# wespi-nano_3.net
KiCad netlist of a schematic drawn in EAGLE
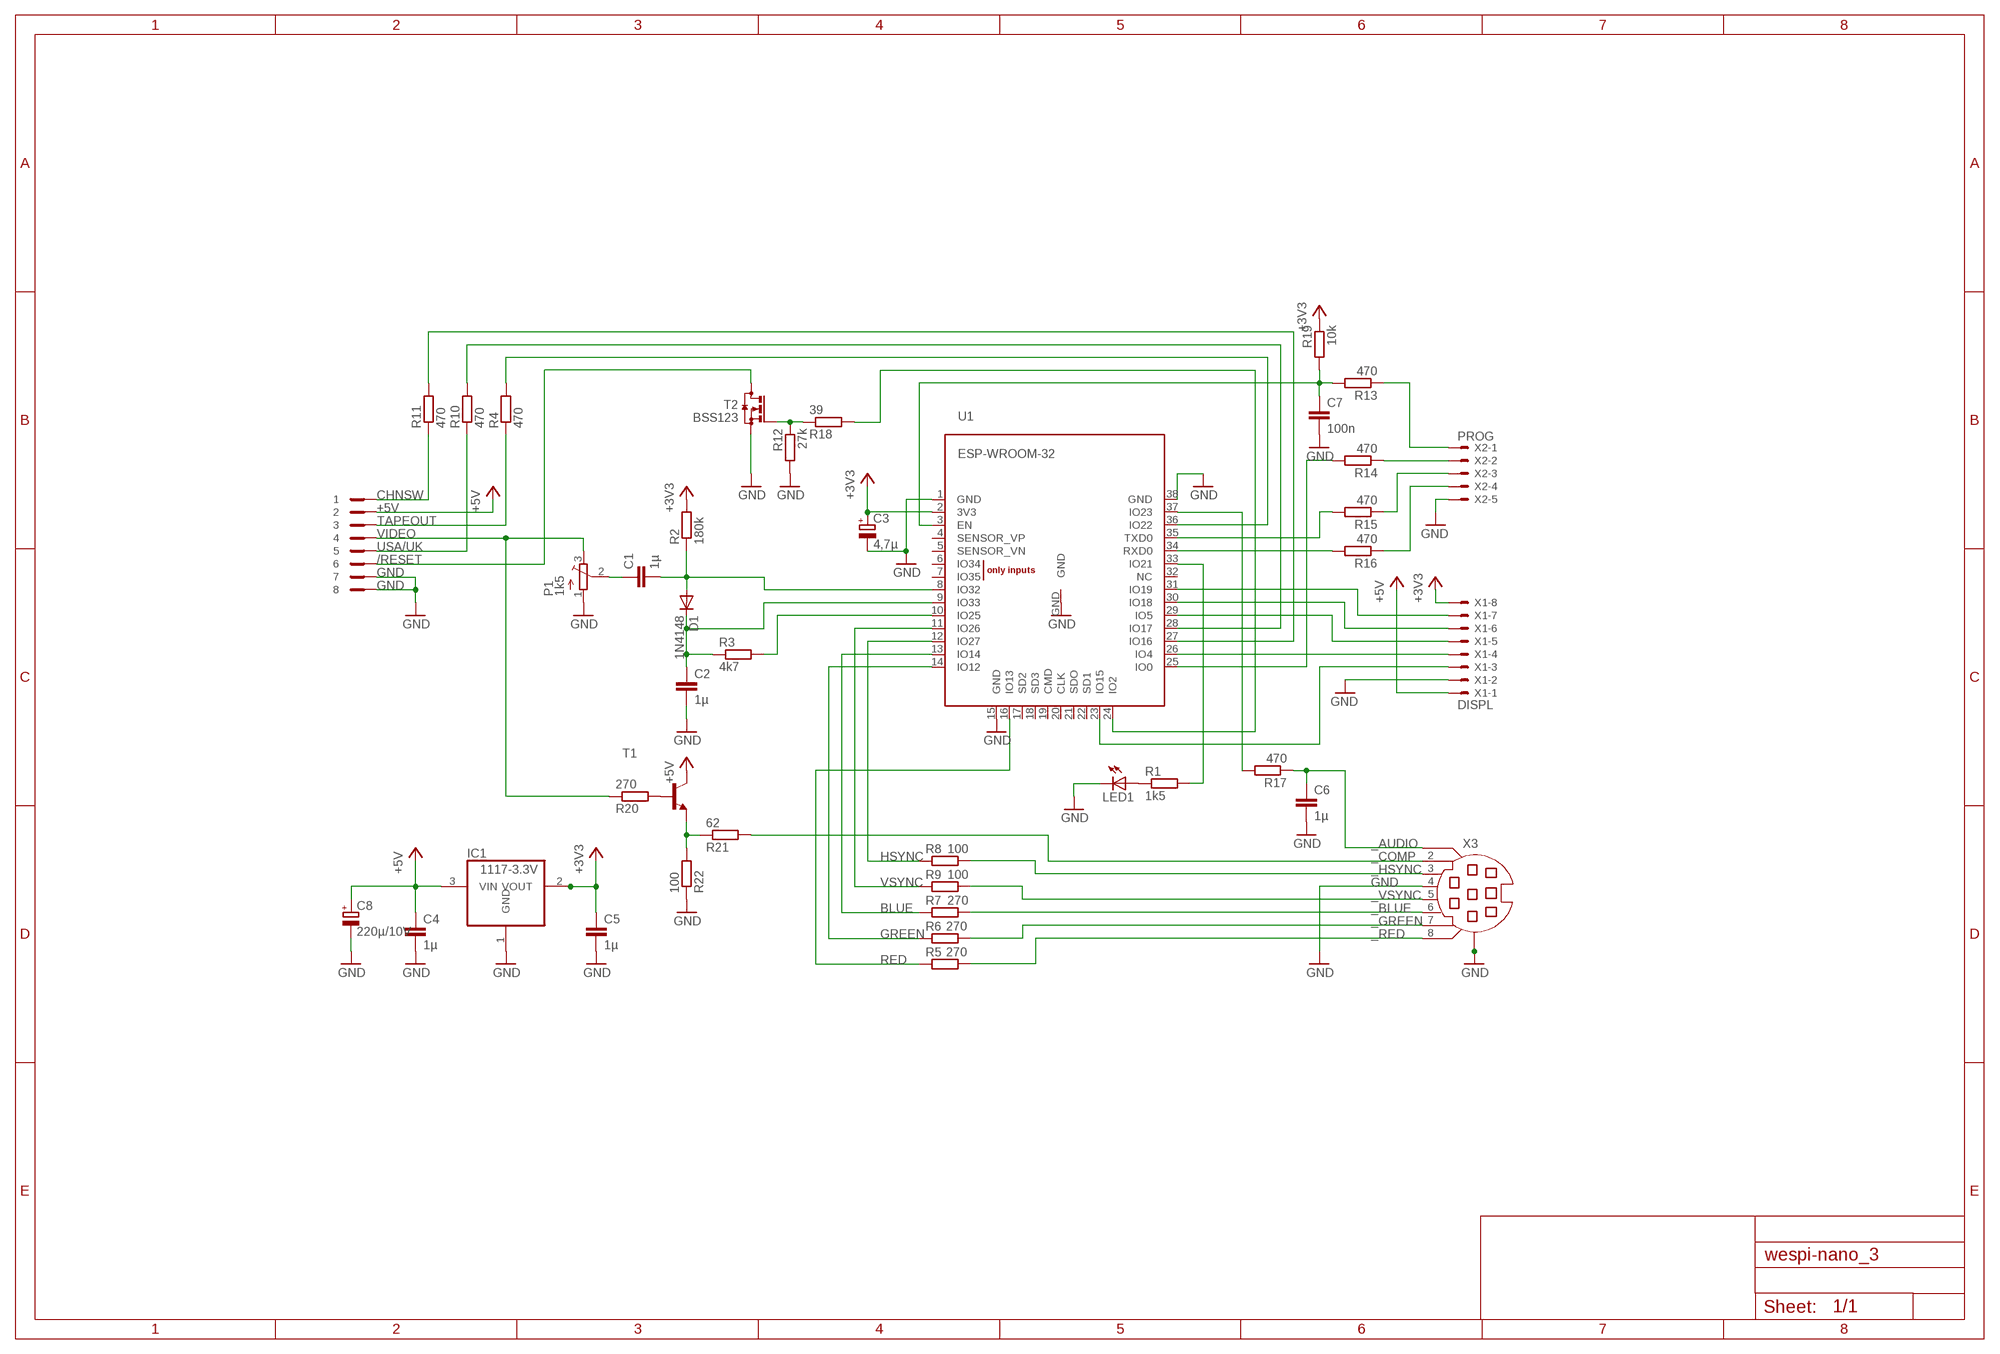
[diagram p0: schematic, sheet 1]

(export (version "E")
  (design (tool "Eeschema 10.0.6"))
  (components
    (comp (ref "C1")
      (value "1µ")
      (footprint "eagle-import:C0805")
      (libsource (lib "eagle-import") (part "C-EUC0805"))
    )
    (comp (ref "C2")
      (value "1µ")
      (footprint "eagle-import:C0805")
      (libsource (lib "eagle-import") (part "C-EUC0805"))
    )
    (comp (ref "C3")
      (value "4,7µ")
      (footprint "eagle-import:153CLV-0405")
      (libsource (lib "eagle-import") (part "CPOL-EU153CLV-0405"))
    )
    (comp (ref "C4")
      (value "1µ")
      (footprint "eagle-import:C0805")
      (libsource (lib "eagle-import") (part "C-EUC0805"))
    )
    (comp (ref "C5")
      (value "1µ")
      (footprint "eagle-import:C0805")
      (libsource (lib "eagle-import") (part "C-EUC0805"))
    )
    (comp (ref "C6")
      (value "1µ")
      (footprint "eagle-import:C0805")
      (libsource (lib "eagle-import") (part "C-EUC0805"))
    )
    (comp (ref "C7")
      (value "100n")
      (footprint "eagle-import:C0805")
      (libsource (lib "eagle-import") (part "C-EUC0805"))
    )
    (comp (ref "C8")
      (value "220µ/10V")
      (footprint "eagle-import:E2,5-6")
      (libsource (lib "eagle-import") (part "rcl_CPOL-EUE2.5-6"))
    )
    (comp (ref "D1")
      (value "1N4148")
      (footprint "eagle-import:SOD-123_MINI-SMA")
      (libsource (lib "eagle-import") (part "CGRM400-G1"))
    )
    (comp (ref "IC1")
      (value "1117-3.3V")
      (footprint "eagle-import:SOT223")
      (libsource (lib "eagle-import") (part "REG1117"))
    )
    (comp (ref "K6")
      (value "PINHEAD-2X4")
      (footprint "eagle-import:PINHEAD2X4")
      (libsource (lib "eagle-import") (part "PINHEAD-2X4"))
    )
    (comp (ref "LED1")
      (value "LEDSML0805")
      (footprint "eagle-import:SML0805")
      (libsource (lib "eagle-import") (part "LEDSML0805"))
    )
    (comp (ref "P1")
      (value "1k5")
      (footprint "eagle-import:3223G")
      (libsource (lib "eagle-import") (part "TRIM_EU-3223G"))
    )
    (comp (ref "R1")
      (value "1k5")
      (footprint "eagle-import:R0805")
      (libsource (lib "eagle-import") (part "R-EU_R0805"))
    )
    (comp (ref "R2")
      (value "180k")
      (footprint "eagle-import:R0805")
      (libsource (lib "eagle-import") (part "R-EU_R0805"))
    )
    (comp (ref "R3")
      (value "4k7")
      (footprint "eagle-import:R0805")
      (libsource (lib "eagle-import") (part "R-EU_R0805"))
    )
    (comp (ref "R4")
      (value "470")
      (footprint "eagle-import:R0805")
      (libsource (lib "eagle-import") (part "R-EU_R0805"))
    )
    (comp (ref "R5")
      (value "270")
      (footprint "eagle-import:R0805")
      (libsource (lib "eagle-import") (part "R-EU_R0805"))
    )
    (comp (ref "R6")
      (value "270")
      (footprint "eagle-import:R0805")
      (libsource (lib "eagle-import") (part "R-EU_R0805"))
    )
    (comp (ref "R7")
      (value "270")
      (footprint "eagle-import:R0805")
      (libsource (lib "eagle-import") (part "R-EU_R0805"))
    )
    (comp (ref "R8")
      (value "100")
      (footprint "eagle-import:R0805")
      (libsource (lib "eagle-import") (part "R-EU_R0805"))
    )
    (comp (ref "R9")
      (value "100")
      (footprint "eagle-import:R0805")
      (libsource (lib "eagle-import") (part "R-EU_R0805"))
    )
    (comp (ref "R10")
      (value "470")
      (footprint "eagle-import:R0805")
      (libsource (lib "eagle-import") (part "R-EU_R0805"))
    )
    (comp (ref "R11")
      (value "470")
      (footprint "eagle-import:R0805")
      (libsource (lib "eagle-import") (part "R-EU_R0805"))
    )
    (comp (ref "R12")
      (value "27k")
      (footprint "eagle-import:R0805")
      (libsource (lib "eagle-import") (part "R-EU_R0805"))
    )
    (comp (ref "R13")
      (value "470")
      (footprint "eagle-import:R0805")
      (libsource (lib "eagle-import") (part "R-EU_R0805"))
    )
    (comp (ref "R14")
      (value "470")
      (footprint "eagle-import:R0805")
      (libsource (lib "eagle-import") (part "R-EU_R0805"))
    )
    (comp (ref "R15")
      (value "470")
      (footprint "eagle-import:R0805")
      (libsource (lib "eagle-import") (part "R-EU_R0805"))
    )
    (comp (ref "R16")
      (value "470")
      (footprint "eagle-import:R0805")
      (libsource (lib "eagle-import") (part "R-EU_R0805"))
    )
    (comp (ref "R17")
      (value "470")
      (footprint "eagle-import:R0805")
      (libsource (lib "eagle-import") (part "R-EU_R0805"))
    )
    (comp (ref "R18")
      (value "39")
      (footprint "eagle-import:R0805")
      (libsource (lib "eagle-import") (part "R-EU_R0805"))
    )
    (comp (ref "R19")
      (value "10k")
      (footprint "eagle-import:R0805")
      (libsource (lib "eagle-import") (part "R-EU_R0805"))
    )
    (comp (ref "R20")
      (value "270")
      (footprint "eagle-import:R0805")
      (libsource (lib "eagle-import") (part "R-EU_R0805"))
    )
    (comp (ref "R21")
      (value "62")
      (footprint "eagle-import:R0805")
      (libsource (lib "eagle-import") (part "R-EU_R0805"))
    )
    (comp (ref "R22")
      (value "100")
      (footprint "eagle-import:R0805")
      (libsource (lib "eagle-import") (part "R-EU_R0805"))
    )
    (comp (ref "T1")
      (value "BC847-NPN-SOT23-BEC")
      (footprint "eagle-import:SOT23-BEC")
      (libsource (lib "eagle-import") (part "-NPN-SOT23-BECBC847"))
    )
    (comp (ref "T2")
      (value "BSS123")
      (footprint "eagle-import:SOT23")
      (libsource (lib "eagle-import") (part "BSS123"))
    )
    (comp (ref "U1")
      (value "ESP-WROOM-32")
      (footprint "eagle-import:ESP-WROOM-32")
      (libsource (lib "eagle-import") (part "ESP-WROOM-32"))
    )
    (comp (ref "X1")
      (value "DISPL")
      (footprint "eagle-import:53047-08")
      (fields (field (name "MPN") "53047-0810"))
      (libsource (lib "eagle-import") (part "53?-08047"))
    )
    (comp (ref "X2")
      (value "PROG")
      (footprint "eagle-import:53047-05")
      (fields (field (name "MF") "MOLEX") (field (name "MPN") "53047-0510"))
      (libsource (lib "eagle-import") (part "53?-05047"))
    )
    (comp (ref "X3")
      (value "MINI-DIN-8")
      (footprint "eagle-import:MINI-DIN-8")
      (libsource (lib "eagle-import") (part "MINI-DIN-8"))
    )
  )
  (nets
    (net (code "1") (name "+3V3") (class "Default")
      (node (ref "C3") (pin "+") (pinfunction "+_+") (pintype "passive"))
      (node (ref "C5") (pin "1") (pinfunction "1_1") (pintype "passive"))
      (node (ref "IC1") (pin "2") (pinfunction "VOUT_2") (pintype "output"))
      (node (ref "IC1") (pin "4") (pinfunction "VOUT1_4") (pintype "output"))
      (node (ref "R19") (pin "1") (pinfunction "1_1") (pintype "passive"))
      (node (ref "R2") (pin "2") (pinfunction "2_2") (pintype "passive"))
      (node (ref "U1") (pin "2") (pinfunction "3V3_2") (pintype "bidirectional"))
      (node (ref "X1") (pin "8") (pinfunction "S_8") (pintype "passive"))
    )
    (net (code "2") (name "+5V") (class "Default")
      (node (ref "C4") (pin "1") (pinfunction "1_1") (pintype "passive"))
      (node (ref "C8") (pin "+") (pinfunction "+_+") (pintype "passive"))
      (node (ref "IC1") (pin "3") (pinfunction "VIN_3") (pintype "input"))
      (node (ref "K6") (pin "2") (pinfunction "2_2") (pintype "bidirectional"))
      (node (ref "T1") (pin "C") (pinfunction "C_C") (pintype "passive"))
      (node (ref "X1") (pin "1") (pinfunction "S_1") (pintype "passive"))
    )
    (net (code "3") (name "/BLUE") (class "Default")
      (node (ref "R7") (pin "1") (pinfunction "1_1") (pintype "passive"))
      (node (ref "U1") (pin "13") (pinfunction "IO14_13") (pintype "bidirectional"))
    )
    (net (code "4") (name "/CHNSW") (class "Default")
      (node (ref "K6") (pin "1") (pinfunction "1_1") (pintype "bidirectional"))
      (node (ref "R11") (pin "1") (pinfunction "1_1") (pintype "passive"))
    )
    (net (code "5") (name "/GREEN") (class "Default")
      (node (ref "R6") (pin "1") (pinfunction "1_1") (pintype "passive"))
      (node (ref "U1") (pin "14") (pinfunction "IO12_14") (pintype "bidirectional"))
    )
    (net (code "6") (name "/HSYNC") (class "Default")
      (node (ref "R8") (pin "1") (pinfunction "1_1") (pintype "passive"))
      (node (ref "U1") (pin "12") (pinfunction "IO27_12") (pintype "bidirectional"))
    )
    (net (code "7") (name "/RED") (class "Default")
      (node (ref "R5") (pin "1") (pinfunction "1_1") (pintype "passive"))
      (node (ref "U1") (pin "16") (pinfunction "IO13_16") (pintype "bidirectional"))
    )
    (net (code "8") (name "/TAPEOUT") (class "Default")
      (node (ref "R4") (pin "2") (pinfunction "2_2") (pintype "passive"))
      (node (ref "U1") (pin "36") (pinfunction "IO22_36") (pintype "bidirectional"))
    )
    (net (code "9") (name "/USA{slash}UK") (class "Default")
      (node (ref "K6") (pin "5") (pinfunction "5_5") (pintype "bidirectional"))
      (node (ref "R10") (pin "1") (pinfunction "1_1") (pintype "passive"))
    )
    (net (code "10") (name "/VIDEO") (class "Default")
      (node (ref "K6") (pin "4") (pinfunction "4_4") (pintype "bidirectional"))
      (node (ref "P1") (pin "3") (pinfunction "E_3") (pintype "passive"))
      (node (ref "R20") (pin "1") (pinfunction "1_1") (pintype "passive"))
    )
    (net (code "11") (name "/VSYNC") (class "Default")
      (node (ref "R9") (pin "1") (pinfunction "1_1") (pintype "passive"))
      (node (ref "U1") (pin "11") (pinfunction "IO26_11") (pintype "bidirectional"))
    )
    (net (code "12") (name "/_AUDIO") (class "Default")
      (node (ref "C6") (pin "1") (pinfunction "1_1") (pintype "passive"))
      (node (ref "R17") (pin "1") (pinfunction "1_1") (pintype "passive"))
      (node (ref "X3") (pin "1") (pinfunction "1_1") (pintype "passive"))
    )
    (net (code "13") (name "/_BLUE") (class "Default")
      (node (ref "R7") (pin "2") (pinfunction "2_2") (pintype "passive"))
      (node (ref "X3") (pin "6") (pinfunction "6_6") (pintype "passive"))
    )
    (net (code "14") (name "/_COMP") (class "Default")
      (node (ref "R21") (pin "2") (pinfunction "2_2") (pintype "passive"))
      (node (ref "X3") (pin "2") (pinfunction "2_2") (pintype "passive"))
    )
    (net (code "15") (name "/_GREEN") (class "Default")
      (node (ref "R6") (pin "2") (pinfunction "2_2") (pintype "passive"))
      (node (ref "X3") (pin "7") (pinfunction "7_7") (pintype "passive"))
    )
    (net (code "16") (name "/_HSYNC") (class "Default")
      (node (ref "R8") (pin "2") (pinfunction "2_2") (pintype "passive"))
      (node (ref "X3") (pin "3") (pinfunction "3_3") (pintype "passive"))
    )
    (net (code "17") (name "/_RED") (class "Default")
      (node (ref "R5") (pin "2") (pinfunction "2_2") (pintype "passive"))
      (node (ref "X3") (pin "8") (pinfunction "8_8") (pintype "passive"))
    )
    (net (code "18") (name "/_VSYNC") (class "Default")
      (node (ref "R9") (pin "2") (pinfunction "2_2") (pintype "passive"))
      (node (ref "X3") (pin "5") (pinfunction "5_5") (pintype "passive"))
    )
    (net (code "19") (name "/{slash}RESET") (class "Default")
      (node (ref "K6") (pin "6") (pinfunction "6_6") (pintype "bidirectional"))
      (node (ref "T2") (pin "3") (pinfunction "D_3") (pintype "passive"))
    )
    (net (code "20") (name "GND") (class "Default")
      (node (ref "C2") (pin "2") (pinfunction "2_2") (pintype "passive"))
      (node (ref "C3") (pin "-") (pinfunction "-_-") (pintype "passive"))
      (node (ref "C4") (pin "2") (pinfunction "2_2") (pintype "passive"))
      (node (ref "C5") (pin "2") (pinfunction "2_2") (pintype "passive"))
      (node (ref "C6") (pin "2") (pinfunction "2_2") (pintype "passive"))
      (node (ref "C7") (pin "2") (pinfunction "2_2") (pintype "passive"))
      (node (ref "C8") (pin "-") (pinfunction "-_-") (pintype "passive"))
      (node (ref "IC1") (pin "1") (pinfunction "GND_1") (pintype "power_in"))
      (node (ref "K6") (pin "7") (pinfunction "7_7") (pintype "bidirectional"))
      (node (ref "K6") (pin "8") (pinfunction "8_8") (pintype "bidirectional"))
      (node (ref "LED1") (pin "C") (pinfunction "C_C") (pintype "passive"))
      (node (ref "P1") (pin "1") (pinfunction "A_1") (pintype "passive"))
      (node (ref "R12") (pin "2") (pinfunction "2_2") (pintype "passive"))
      (node (ref "R22") (pin "1") (pinfunction "1_1") (pintype "passive"))
      (node (ref "T2") (pin "2") (pinfunction "S_2") (pintype "passive"))
      (node (ref "U1") (pin "1") (pinfunction "GND_1") (pintype "bidirectional"))
      (node (ref "U1") (pin "15") (pinfunction "GND_15") (pintype "bidirectional"))
      (node (ref "U1") (pin "38") (pinfunction "GND_38") (pintype "bidirectional"))
      (node (ref "U1") (pin "GND") (pinfunction "GND_GND") (pintype "bidirectional"))
      (node (ref "X1") (pin "2") (pinfunction "S_2") (pintype "passive"))
      (node (ref "X2") (pin "5") (pinfunction "S_5") (pintype "passive"))
      (node (ref "X3") (pin "4") (pinfunction "4_4") (pintype "passive"))
      (node (ref "X3") (pin "G") (pinfunction "G1_G") (pintype "passive"))
      (node (ref "X3") (pin "G1") (pinfunction "G2_G1") (pintype "passive"))
      (node (ref "X3") (pin "G2") (pinfunction "G3_G2") (pintype "passive"))
    )
    (net (code "21") (name "Net-(K6-Pad3)") (class "Default")
      (node (ref "K6") (pin "3") (pinfunction "3_3") (pintype "bidirectional"))
      (node (ref "R4") (pin "1") (pinfunction "1_1") (pintype "passive"))
    )
    (net (code "22") (name "Net-(LED1-PadA)") (class "Default")
      (node (ref "LED1") (pin "A") (pinfunction "A_A") (pintype "passive"))
      (node (ref "R1") (pin "1") (pinfunction "1_1") (pintype "passive"))
    )
    (net (code "23") (name "Net-(P1-S)") (class "Default")
      (node (ref "C1") (pin "1") (pinfunction "1_1") (pintype "passive"))
      (node (ref "P1") (pin "2") (pinfunction "S_2") (pintype "passive"))
    )
    (net (code "24") (name "Net-(R20-Pad2)") (class "Default")
      (node (ref "R20") (pin "2") (pinfunction "2_2") (pintype "passive"))
      (node (ref "T1") (pin "B") (pinfunction "B_B") (pintype "passive"))
    )
    (net (code "25") (name "Net-(R21-Pad1)") (class "Default")
      (node (ref "R21") (pin "1") (pinfunction "1_1") (pintype "passive"))
      (node (ref "R22") (pin "2") (pinfunction "2_2") (pintype "passive"))
      (node (ref "T1") (pin "E") (pinfunction "E_E") (pintype "passive"))
    )
    (net (code "26") (name "Net-(T2-G)") (class "Default")
      (node (ref "R12") (pin "1") (pinfunction "1_1") (pintype "passive"))
      (node (ref "R18") (pin "1") (pinfunction "1_1") (pintype "passive"))
      (node (ref "T2") (pin "1") (pinfunction "G_1") (pintype "passive"))
    )
    (net (code "27") (name "Net-(U1-EN)") (class "Default")
      (node (ref "C7") (pin "1") (pinfunction "1_1") (pintype "passive"))
      (node (ref "R13") (pin "2") (pinfunction "2_2") (pintype "passive"))
      (node (ref "R19") (pin "2") (pinfunction "2_2") (pintype "passive"))
      (node (ref "U1") (pin "3") (pinfunction "EN_3") (pintype "bidirectional"))
    )
    (net (code "28") (name "Net-(U1-IO0)") (class "Default")
      (node (ref "R14") (pin "2") (pinfunction "2_2") (pintype "passive"))
      (node (ref "U1") (pin "25") (pinfunction "IO0_25") (pintype "bidirectional"))
    )
    (net (code "29") (name "Net-(U1-IO2)") (class "Default")
      (node (ref "R18") (pin "2") (pinfunction "2_2") (pintype "passive"))
      (node (ref "U1") (pin "24") (pinfunction "IO2_24") (pintype "bidirectional"))
    )
    (net (code "30") (name "Net-(U1-IO4)") (class "Default")
      (node (ref "U1") (pin "26") (pinfunction "IO4_26") (pintype "bidirectional"))
      (node (ref "X1") (pin "4") (pinfunction "S_4") (pintype "passive"))
    )
    (net (code "31") (name "Net-(U1-IO5)") (class "Default")
      (node (ref "U1") (pin "29") (pinfunction "IO5_29") (pintype "bidirectional"))
      (node (ref "X1") (pin "5") (pinfunction "S_5") (pintype "passive"))
    )
    (net (code "32") (name "Net-(U1-IO15)") (class "Default")
      (node (ref "U1") (pin "23") (pinfunction "IO15_23") (pintype "bidirectional"))
      (node (ref "X1") (pin "3") (pinfunction "S_3") (pintype "passive"))
    )
    (net (code "33") (name "Net-(U1-IO16)") (class "Default")
      (node (ref "R11") (pin "2") (pinfunction "2_2") (pintype "passive"))
      (node (ref "U1") (pin "27") (pinfunction "IO16_27") (pintype "bidirectional"))
    )
    (net (code "34") (name "Net-(U1-IO17)") (class "Default")
      (node (ref "R10") (pin "2") (pinfunction "2_2") (pintype "passive"))
      (node (ref "U1") (pin "28") (pinfunction "IO17_28") (pintype "bidirectional"))
    )
    (net (code "35") (name "Net-(U1-IO18)") (class "Default")
      (node (ref "U1") (pin "30") (pinfunction "IO18_30") (pintype "bidirectional"))
      (node (ref "X1") (pin "6") (pinfunction "S_6") (pintype "passive"))
    )
    (net (code "36") (name "Net-(U1-IO19)") (class "Default")
      (node (ref "U1") (pin "31") (pinfunction "IO19_31") (pintype "bidirectional"))
      (node (ref "X1") (pin "7") (pinfunction "S_7") (pintype "passive"))
    )
    (net (code "37") (name "Net-(U1-IO21)") (class "Default")
      (node (ref "R1") (pin "2") (pinfunction "2_2") (pintype "passive"))
      (node (ref "U1") (pin "33") (pinfunction "IO21_33") (pintype "bidirectional"))
    )
    (net (code "38") (name "Net-(U1-IO23)") (class "Default")
      (node (ref "R17") (pin "2") (pinfunction "2_2") (pintype "passive"))
      (node (ref "U1") (pin "37") (pinfunction "IO23_37") (pintype "bidirectional"))
    )
    (net (code "39") (name "Net-(U1-IO25)") (class "Default")
      (node (ref "R3") (pin "2") (pinfunction "2_2") (pintype "passive"))
      (node (ref "U1") (pin "10") (pinfunction "IO25_10") (pintype "bidirectional"))
    )
    (net (code "40") (name "Net-(U1-IO32)") (class "Default")
      (node (ref "C1") (pin "2") (pinfunction "2_2") (pintype "passive"))
      (node (ref "D1") (pin "A") (pinfunction "A_A") (pintype "passive"))
      (node (ref "R2") (pin "1") (pinfunction "1_1") (pintype "passive"))
      (node (ref "U1") (pin "8") (pinfunction "IO32_8") (pintype "bidirectional"))
    )
    (net (code "41") (name "Net-(U1-IO33)") (class "Default")
      (node (ref "C2") (pin "1") (pinfunction "1_1") (pintype "passive"))
      (node (ref "D1") (pin "C") (pinfunction "C_C") (pintype "passive"))
      (node (ref "R3") (pin "1") (pinfunction "1_1") (pintype "passive"))
      (node (ref "U1") (pin "9") (pinfunction "IO33_9") (pintype "bidirectional"))
    )
    (net (code "42") (name "Net-(U1-RXD0)") (class "Default")
      (node (ref "R16") (pin "2") (pinfunction "2_2") (pintype "passive"))
      (node (ref "U1") (pin "34") (pinfunction "RXD0_34") (pintype "bidirectional"))
    )
    (net (code "43") (name "Net-(U1-TXD0)") (class "Default")
      (node (ref "R15") (pin "2") (pinfunction "2_2") (pintype "passive"))
      (node (ref "U1") (pin "35") (pinfunction "TXD0_35") (pintype "bidirectional"))
    )
    (net (code "44") (name "Net-(X2A-S)") (class "Default")
      (node (ref "R13") (pin "1") (pinfunction "1_1") (pintype "passive"))
      (node (ref "X2") (pin "1") (pinfunction "S_1") (pintype "passive"))
    )
    (net (code "45") (name "Net-(X2B-S)") (class "Default")
      (node (ref "R14") (pin "1") (pinfunction "1_1") (pintype "passive"))
      (node (ref "X2") (pin "2") (pinfunction "S_2") (pintype "passive"))
    )
    (net (code "46") (name "Net-(X2C-S)") (class "Default")
      (node (ref "R15") (pin "1") (pinfunction "1_1") (pintype "passive"))
      (node (ref "X2") (pin "3") (pinfunction "S_3") (pintype "passive"))
    )
    (net (code "47") (name "Net-(X2D-S)") (class "Default")
      (node (ref "R16") (pin "1") (pinfunction "1_1") (pintype "passive"))
      (node (ref "X2") (pin "4") (pinfunction "S_4") (pintype "passive"))
    )
    (net (code "48") (name "unconnected-(U1-CLK-Pad20)") (class "Default")
      (node (ref "U1") (pin "20") (pinfunction "CLK_20") (pintype "bidirectional"))
    )
    (net (code "49") (name "unconnected-(U1-CMD-Pad19)") (class "Default")
      (node (ref "U1") (pin "19") (pinfunction "CMD_19") (pintype "bidirectional"))
    )
    (net (code "50") (name "unconnected-(U1-IO34-Pad6)") (class "Default")
      (node (ref "U1") (pin "6") (pinfunction "IO34_6") (pintype "input"))
    )
    (net (code "51") (name "unconnected-(U1-IO35-Pad7)") (class "Default")
      (node (ref "U1") (pin "7") (pinfunction "IO35_7") (pintype "input"))
    )
    (net (code "52") (name "unconnected-(U1-NC-Pad32)") (class "Default")
      (node (ref "U1") (pin "32") (pinfunction "NC_32") (pintype "bidirectional"))
    )
    (net (code "53") (name "unconnected-(U1-SD1-Pad22)") (class "Default")
      (node (ref "U1") (pin "22") (pinfunction "SD1_22") (pintype "bidirectional"))
    )
    (net (code "54") (name "unconnected-(U1-SD2-Pad17)") (class "Default")
      (node (ref "U1") (pin "17") (pinfunction "SD2_17") (pintype "bidirectional"))
    )
    (net (code "55") (name "unconnected-(U1-SD3-Pad18)") (class "Default")
      (node (ref "U1") (pin "18") (pinfunction "SD3_18") (pintype "bidirectional"))
    )
    (net (code "56") (name "unconnected-(U1-SDO-Pad21)") (class "Default")
      (node (ref "U1") (pin "21") (pinfunction "SDO_21") (pintype "bidirectional"))
    )
    (net (code "57") (name "unconnected-(U1-SENSOR_VN-Pad5)") (class "Default")
      (node (ref "U1") (pin "5") (pinfunction "SENSOR_VN_5") (pintype "input"))
    )
    (net (code "58") (name "unconnected-(U1-SENSOR_VP-Pad4)") (class "Default")
      (node (ref "U1") (pin "4") (pinfunction "SENSOR_VP_4") (pintype "input"))
    )
  )
)
